# BK8000L_BREADBOARD_BUDDY.net
KiCad netlist of a schematic drawn in EAGLE
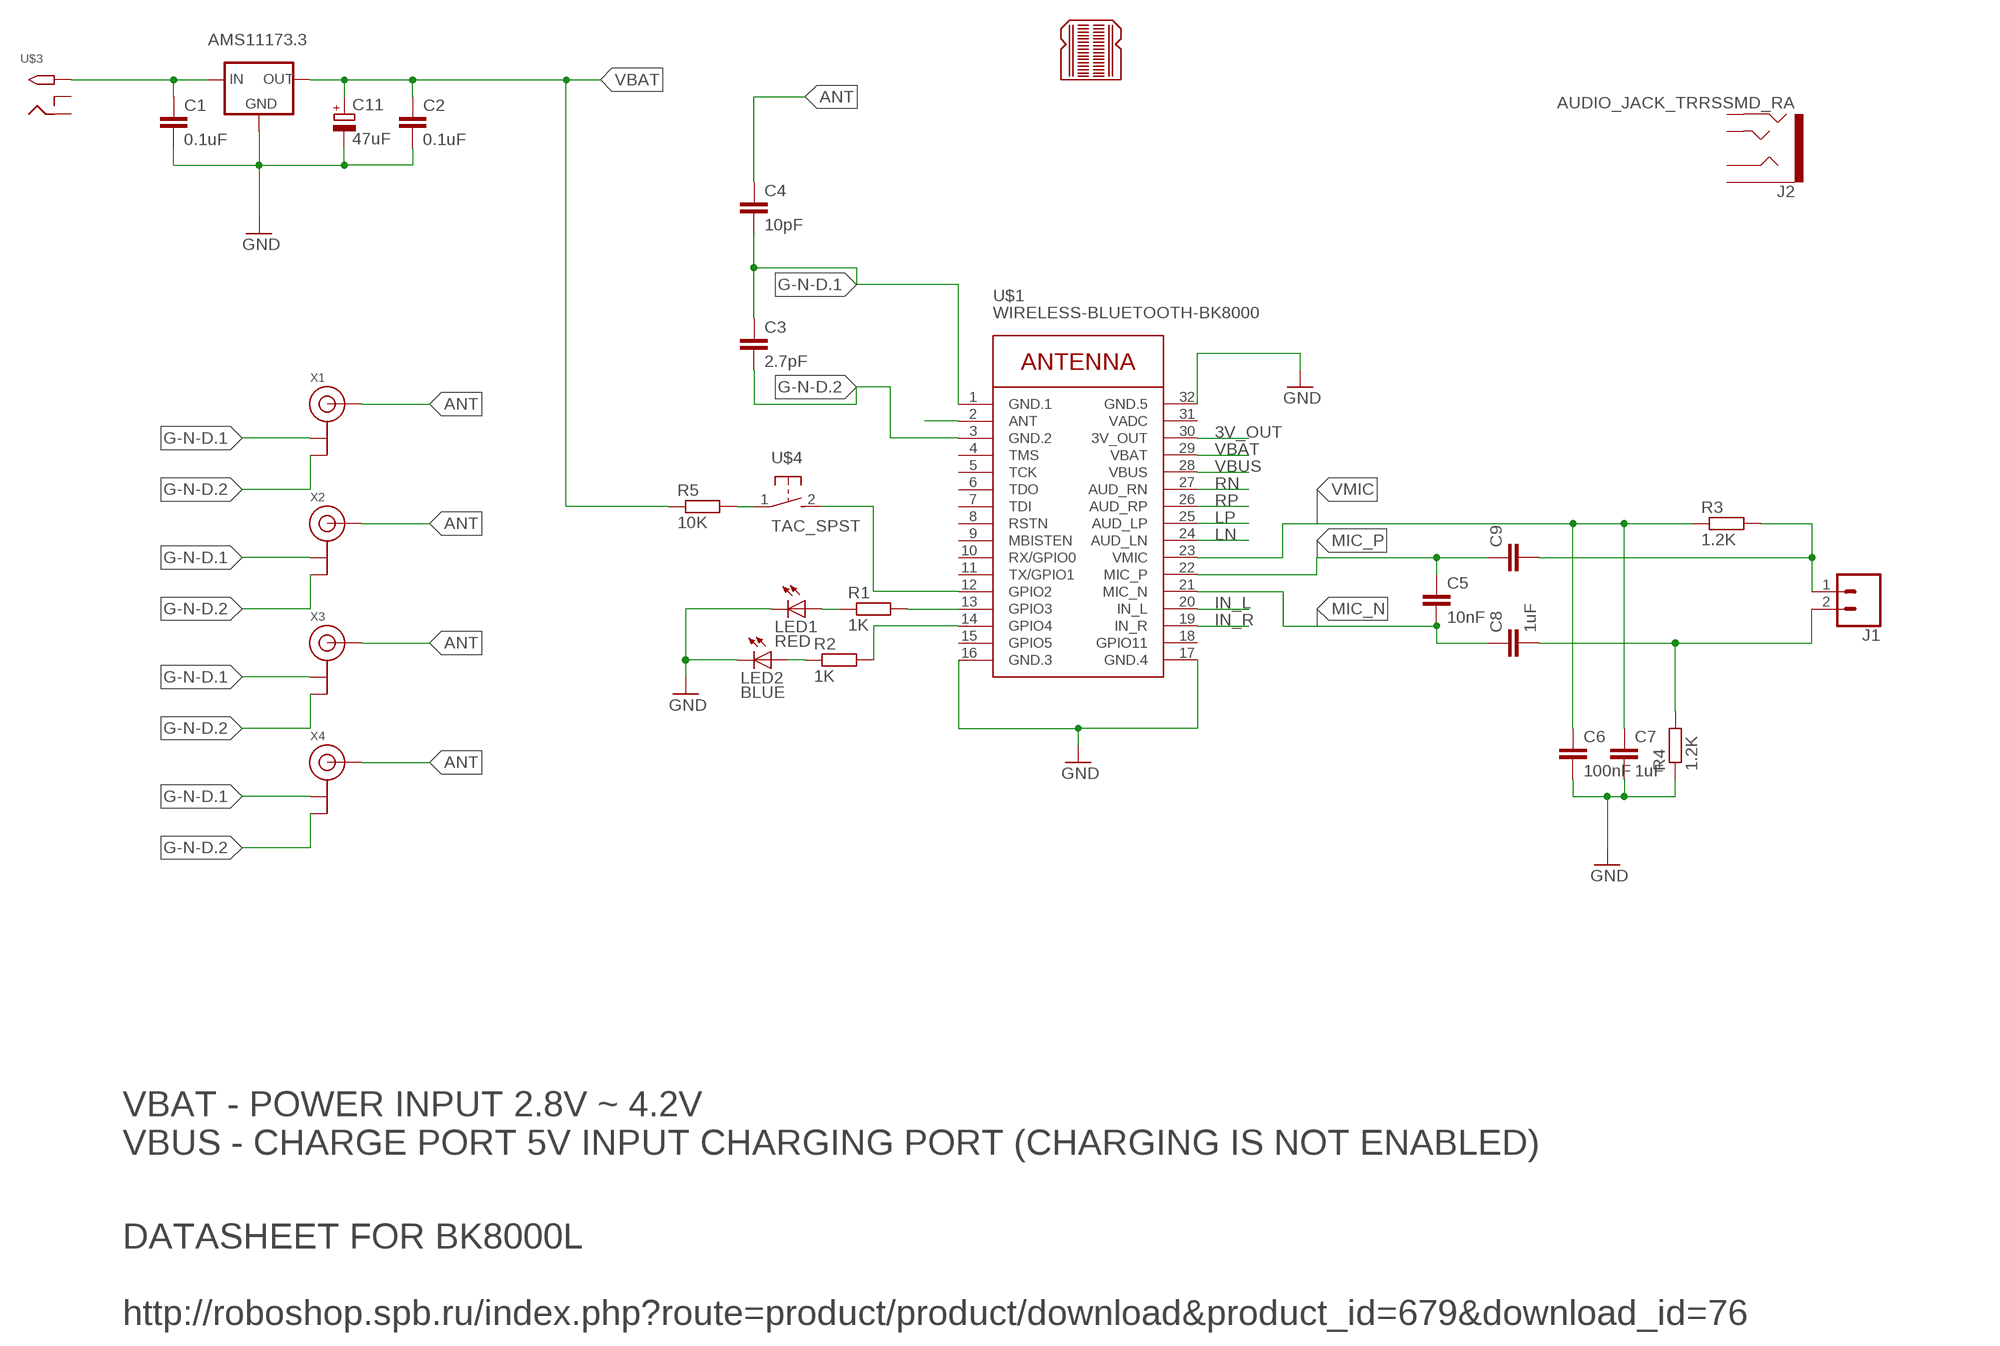
[diagram p0: schematic, sheet 1]

(export (version "E")
  (design (tool "Eeschema 10.0.6"))
  (components
    (comp (ref "C1")
      (value "0.1uF")
      (footprint "eagle-import:C1206")
      (libsource (lib "eagle-import") (part "C-EUC1206"))
    )
    (comp (ref "C2")
      (value "0.1uF")
      (footprint "eagle-import:C1206")
      (libsource (lib "eagle-import") (part "C-EUC1206"))
    )
    (comp (ref "C3")
      (value "2.7pF")
      (footprint "eagle-import:C1206")
      (libsource (lib "eagle-import") (part "C-EUC1206"))
    )
    (comp (ref "C4")
      (value "10pF")
      (footprint "eagle-import:C1206")
      (libsource (lib "eagle-import") (part "C-EUC1206"))
    )
    (comp (ref "C5")
      (value "10nF")
      (footprint "eagle-import:C0603")
      (libsource (lib "eagle-import") (part "C-EUC0603"))
    )
    (comp (ref "C6")
      (value "100nF")
      (footprint "eagle-import:C0603")
      (libsource (lib "eagle-import") (part "C-EUC0603"))
    )
    (comp (ref "C7")
      (value "1uF")
      (footprint "eagle-import:C0603")
      (libsource (lib "eagle-import") (part "C-EUC0603"))
    )
    (comp (ref "C8")
      (value "1uF")
      (footprint "eagle-import:C0603")
      (libsource (lib "eagle-import") (part "C-EUC0603"))
    )
    (comp (ref "C9")
      (value "C-EUC0603")
      (footprint "eagle-import:C0603")
      (libsource (lib "eagle-import") (part "C-EUC0603"))
    )
    (comp (ref "C11")
      (value "47uF")
      (footprint "eagle-import:SMC_D")
      (libsource (lib "eagle-import") (part "CPOL-EUSMCD"))
    )
    (comp (ref "J1")
      (value "CONN_02LOCK")
      (footprint "eagle-import:1X02_LOCK")
      (libsource (lib "eagle-import") (part "CONN_02LOCK"))
    )
    (comp (ref "J2")
      (value "AUDIO_JACK_TRRSSMD_RA")
      (footprint "eagle-import:AUDIO_JACK_3.5MM_TRRS_SMD_RA")
      (libsource (lib "eagle-import") (part "AUDIO_JACK_TRRSSMD_RA"))
    )
    (comp (ref "LED1")
      (value "RED")
      (footprint "eagle-import:CHIPLED_1206")
      (libsource (lib "eagle-import") (part "LEDCHIPLED_1206"))
    )
    (comp (ref "LED2")
      (value "BLUE")
      (footprint "eagle-import:CHIPLED_1206")
      (libsource (lib "eagle-import") (part "LEDCHIPLED_1206"))
    )
    (comp (ref "LOGO1")
      (value "BREADBOARD_PATTERN")
      (footprint "eagle-import:BREADBOARD_SPACING")
      (libsource (lib "eagle-import") (part "BREADBOARD_PATTERN"))
    )
    (comp (ref "R1")
      (value "1K")
      (footprint "eagle-import:R1206")
      (libsource (lib "eagle-import") (part "R-EU_R1206"))
    )
    (comp (ref "R2")
      (value "1K")
      (footprint "eagle-import:R1206")
      (libsource (lib "eagle-import") (part "R-EU_R1206"))
    )
    (comp (ref "R3")
      (value "1.2K")
      (footprint "eagle-import:R0603")
      (libsource (lib "eagle-import") (part "R-EU_R0603"))
    )
    (comp (ref "R4")
      (value "1.2K")
      (footprint "eagle-import:R0603")
      (libsource (lib "eagle-import") (part "R-EU_R0603"))
    )
    (comp (ref "R5")
      (value "10K")
      (footprint "eagle-import:R0603")
      (libsource (lib "eagle-import") (part "R-EU_R0603"))
    )
    (comp (ref "U$1")
      (value "WIRELESS-BLUETOOTH-BK8000")
      (footprint "eagle-import:WIRELESS-BLUETOOTH-BK8000")
      (libsource (lib "eagle-import") (part "WIRELESS-BLUETOOTH-BK8000"))
    )
    (comp (ref "U$2")
      (value "AMS11173.3")
      (footprint "eagle-import:SOT223")
      (libsource (lib "eagle-import") (part "AMS11173.3"))
    )
    (comp (ref "U$3")
      (value "2.1MMJACKMTS")
      (footprint "eagle-import:PJ-102B")
      (libsource (lib "eagle-import") (part "2.1MMJACKMTS"))
    )
    (comp (ref "U$4")
      (value "TAC_SPST")
      (footprint "eagle-import:TACTILE-SPST")
      (libsource (lib "eagle-import") (part "TAC_SPST"))
    )
    (comp (ref "X1")
      (value "ANTENNA_U.FL")
      (footprint "eagle-import:U.FL")
      (libsource (lib "eagle-import") (part "ANTENNA_U.FL"))
    )
    (comp (ref "X2")
      (value "ANTENNA_U.FL")
      (footprint "eagle-import:U.FL")
      (libsource (lib "eagle-import") (part "ANTENNA_U.FL"))
    )
    (comp (ref "X3")
      (value "ANTENNA_U.FL")
      (footprint "eagle-import:U.FL")
      (libsource (lib "eagle-import") (part "ANTENNA_U.FL"))
    )
    (comp (ref "X4")
      (value "ANTENNA_U.FL")
      (footprint "eagle-import:U.FL")
      (libsource (lib "eagle-import") (part "ANTENNA_U.FL"))
    )
  )
  (nets
    (net (code "1") (name "/3V_OUT") (class "Default")
      (node (ref "U$1") (pin "30") (pinfunction "3V_OUT_30") (pintype "power_in"))
    )
    (net (code "2") (name "/IN_L") (class "Default")
      (node (ref "U$1") (pin "20") (pinfunction "IN_L_20") (pintype "input"))
    )
    (net (code "3") (name "/IN_R") (class "Default")
      (node (ref "U$1") (pin "19") (pinfunction "IN_R_19") (pintype "input"))
    )
    (net (code "4") (name "/LN") (class "Default")
      (node (ref "U$1") (pin "24") (pinfunction "AUD_LN_24") (pintype "output"))
    )
    (net (code "5") (name "/LP") (class "Default")
      (node (ref "U$1") (pin "25") (pinfunction "AUD_LP_25") (pintype "output"))
    )
    (net (code "6") (name "/RN") (class "Default")
      (node (ref "U$1") (pin "27") (pinfunction "AUD_RN_27") (pintype "output"))
    )
    (net (code "7") (name "/RP") (class "Default")
      (node (ref "U$1") (pin "26") (pinfunction "AUD_RP_26") (pintype "output"))
    )
    (net (code "8") (name "/VADC") (class "Default")
      (node (ref "U$1") (pin "31") (pinfunction "VADC_31") (pintype "power_in"))
    )
    (net (code "9") (name "/VBUS") (class "Default")
      (node (ref "U$1") (pin "28") (pinfunction "VBUS_28") (pintype "passive"))
    )
    (net (code "10") (name "ANT") (class "Default")
      (node (ref "C4") (pin "1") (pinfunction "1_1") (pintype "passive"))
      (node (ref "U$1") (pin "2") (pinfunction "ANT_2") (pintype "passive"))
      (node (ref "X1") (pin "3") (pinfunction "SIGNAL_3") (pintype "passive"))
      (node (ref "X2") (pin "3") (pinfunction "SIGNAL_3") (pintype "passive"))
      (node (ref "X3") (pin "3") (pinfunction "SIGNAL_3") (pintype "passive"))
      (node (ref "X4") (pin "3") (pinfunction "SIGNAL_3") (pintype "passive"))
    )
    (net (code "11") (name "G-N-D.1") (class "Default")
      (node (ref "C3") (pin "1") (pinfunction "1_1") (pintype "passive"))
      (node (ref "C4") (pin "2") (pinfunction "2_2") (pintype "passive"))
      (node (ref "U$1") (pin "1") (pinfunction "GND.1_1") (pintype "power_in"))
      (node (ref "X1") (pin "1") (pinfunction "GND_1") (pintype "passive"))
      (node (ref "X2") (pin "1") (pinfunction "GND_1") (pintype "passive"))
      (node (ref "X3") (pin "1") (pinfunction "GND_1") (pintype "passive"))
      (node (ref "X4") (pin "1") (pinfunction "GND_1") (pintype "passive"))
    )
    (net (code "12") (name "G-N-D.2") (class "Default")
      (node (ref "C3") (pin "2") (pinfunction "2_2") (pintype "passive"))
      (node (ref "U$1") (pin "3") (pinfunction "GND.2_3") (pintype "power_in"))
      (node (ref "X1") (pin "2") (pinfunction "GND_2") (pintype "passive"))
      (node (ref "X2") (pin "2") (pinfunction "GND_2") (pintype "passive"))
      (node (ref "X3") (pin "2") (pinfunction "GND_2") (pintype "passive"))
      (node (ref "X4") (pin "2") (pinfunction "GND_2") (pintype "passive"))
    )
    (net (code "13") (name "GND") (class "Default")
      (node (ref "C1") (pin "2") (pinfunction "2_2") (pintype "passive"))
      (node (ref "C11") (pin "-") (pinfunction "-_-") (pintype "passive"))
      (node (ref "C2") (pin "2") (pinfunction "2_2") (pintype "passive"))
      (node (ref "C6") (pin "2") (pinfunction "2_2") (pintype "passive"))
      (node (ref "C7") (pin "2") (pinfunction "2_2") (pintype "passive"))
      (node (ref "LED1") (pin "C") (pinfunction "C_C") (pintype "passive"))
      (node (ref "LED2") (pin "C") (pinfunction "C_C") (pintype "passive"))
      (node (ref "R4") (pin "1") (pinfunction "1_1") (pintype "passive"))
      (node (ref "U$1") (pin "16") (pinfunction "GND.3_16") (pintype "power_in"))
      (node (ref "U$1") (pin "17") (pinfunction "GND.4_17") (pintype "power_in"))
      (node (ref "U$1") (pin "32") (pinfunction "GND.5_32") (pintype "power_in"))
      (node (ref "U$2") (pin "1") (pinfunction "GND_1") (pintype "input"))
    )
    (net (code "14") (name "MIC_N") (class "Default")
      (node (ref "C5") (pin "2") (pinfunction "2_2") (pintype "passive"))
      (node (ref "C8") (pin "1") (pinfunction "1_1") (pintype "passive"))
      (node (ref "U$1") (pin "21") (pinfunction "MIC_N_21") (pintype "input"))
    )
    (net (code "15") (name "MIC_P") (class "Default")
      (node (ref "C5") (pin "1") (pinfunction "1_1") (pintype "passive"))
      (node (ref "C9") (pin "1") (pinfunction "1_1") (pintype "passive"))
      (node (ref "U$1") (pin "22") (pinfunction "MIC_P_22") (pintype "input"))
    )
    (net (code "16") (name "Net-(C8-Pad2)") (class "Default")
      (node (ref "C8") (pin "2") (pinfunction "2_2") (pintype "passive"))
      (node (ref "J1") (pin "2") (pinfunction "2_2") (pintype "passive"))
      (node (ref "R4") (pin "2") (pinfunction "2_2") (pintype "passive"))
    )
    (net (code "17") (name "Net-(C9-Pad2)") (class "Default")
      (node (ref "C9") (pin "2") (pinfunction "2_2") (pintype "passive"))
      (node (ref "J1") (pin "1") (pinfunction "1_1") (pintype "passive"))
      (node (ref "R3") (pin "2") (pinfunction "2_2") (pintype "passive"))
    )
    (net (code "18") (name "Net-(LED1-PadA)") (class "Default")
      (node (ref "LED1") (pin "A") (pinfunction "A_A") (pintype "passive"))
      (node (ref "R1") (pin "1") (pinfunction "1_1") (pintype "passive"))
    )
    (net (code "19") (name "Net-(LED2-PadA)") (class "Default")
      (node (ref "LED2") (pin "A") (pinfunction "A_A") (pintype "passive"))
      (node (ref "R2") (pin "1") (pinfunction "1_1") (pintype "passive"))
    )
    (net (code "20") (name "Net-(R5-Pad2)") (class "Default")
      (node (ref "R5") (pin "2") (pinfunction "2_2") (pintype "passive"))
      (node (ref "U$4") (pin "1") (pinfunction "1_1") (pintype "passive"))
    )
    (net (code "21") (name "Net-(U$1-GPIO2)") (class "Default")
      (node (ref "U$1") (pin "12") (pinfunction "GPIO2_12") (pintype "bidirectional"))
      (node (ref "U$4") (pin "2") (pinfunction "2_2") (pintype "passive"))
    )
    (net (code "22") (name "Net-(U$1-GPIO3)") (class "Default")
      (node (ref "R1") (pin "2") (pinfunction "2_2") (pintype "passive"))
      (node (ref "U$1") (pin "13") (pinfunction "GPIO3_13") (pintype "bidirectional"))
    )
    (net (code "23") (name "Net-(U$1-GPIO4)") (class "Default")
      (node (ref "R2") (pin "2") (pinfunction "2_2") (pintype "passive"))
      (node (ref "U$1") (pin "14") (pinfunction "GPIO4_14") (pintype "bidirectional"))
    )
    (net (code "24") (name "Net-(U$2-IN)") (class "Default")
      (node (ref "C1") (pin "1") (pinfunction "1_1") (pintype "passive"))
      (node (ref "U$2") (pin "3") (pinfunction "IN_3") (pintype "input"))
      (node (ref "U$3") (pin "TIP") (pinfunction "TIP_TIP") (pintype "bidirectional"))
    )
    (net (code "25") (name "VBAT") (class "Default")
      (node (ref "C11") (pin "+") (pinfunction "+_+") (pintype "passive"))
      (node (ref "C2") (pin "1") (pinfunction "1_1") (pintype "passive"))
      (node (ref "R5") (pin "1") (pinfunction "1_1") (pintype "passive"))
      (node (ref "U$1") (pin "29") (pinfunction "VBAT_29") (pintype "passive"))
      (node (ref "U$2") (pin "2") (pinfunction "OUT_2") (pintype "passive"))
      (node (ref "U$2") (pin "4") (pinfunction "OUT_4") (pintype "passive"))
    )
    (net (code "26") (name "VMIC") (class "Default")
      (node (ref "C6") (pin "1") (pinfunction "1_1") (pintype "passive"))
      (node (ref "C7") (pin "1") (pinfunction "1_1") (pintype "passive"))
      (node (ref "R3") (pin "1") (pinfunction "1_1") (pintype "passive"))
      (node (ref "U$1") (pin "23") (pinfunction "VMIC_23") (pintype "passive"))
    )
    (net (code "27") (name "unconnected-(J2-PadEARTH)") (class "Default")
      (node (ref "J2") (pin "EARTH") (pinfunction "EARTH_EARTH") (pintype "bidirectional"))
    )
    (net (code "28") (name "unconnected-(J2-PadRING1)") (class "Default")
      (node (ref "J2") (pin "RING1") (pinfunction "RING1_RING1") (pintype "bidirectional"))
    )
    (net (code "29") (name "unconnected-(J2-PadRING2)") (class "Default")
      (node (ref "J2") (pin "RING2") (pinfunction "RING2_RING2") (pintype "bidirectional"))
    )
    (net (code "30") (name "unconnected-(J2-PadTIP)") (class "Default")
      (node (ref "J2") (pin "TIP") (pinfunction "TIP_TIP") (pintype "bidirectional"))
    )
    (net (code "31") (name "unconnected-(U$1-GPIO5-Pad15)") (class "Default")
      (node (ref "U$1") (pin "15") (pinfunction "GPIO5_15") (pintype "bidirectional"))
    )
    (net (code "32") (name "unconnected-(U$1-GPIO11-Pad18)") (class "Default")
      (node (ref "U$1") (pin "18") (pinfunction "GPIO11_18") (pintype "bidirectional"))
    )
    (net (code "33") (name "unconnected-(U$1-MBISTEN-Pad9)") (class "Default")
      (node (ref "U$1") (pin "9") (pinfunction "MBISTEN_9") (pintype "bidirectional"))
    )
    (net (code "34") (name "unconnected-(U$1-RSTN-Pad8)") (class "Default")
      (node (ref "U$1") (pin "8") (pinfunction "RSTN_8") (pintype "bidirectional"))
    )
    (net (code "35") (name "unconnected-(U$1-RX{slash}GPIO0-Pad10)") (class "Default")
      (node (ref "U$1") (pin "10") (pinfunction "RX/GPIO0_10") (pintype "bidirectional"))
    )
    (net (code "36") (name "unconnected-(U$1-TCK-Pad5)") (class "Default")
      (node (ref "U$1") (pin "5") (pinfunction "TCK_5") (pintype "bidirectional"))
    )
    (net (code "37") (name "unconnected-(U$1-TDI-Pad7)") (class "Default")
      (node (ref "U$1") (pin "7") (pinfunction "TDI_7") (pintype "bidirectional"))
    )
    (net (code "38") (name "unconnected-(U$1-TDO-Pad6)") (class "Default")
      (node (ref "U$1") (pin "6") (pinfunction "TDO_6") (pintype "bidirectional"))
    )
    (net (code "39") (name "unconnected-(U$1-TMS-Pad4)") (class "Default")
      (node (ref "U$1") (pin "4") (pinfunction "TMS_4") (pintype "bidirectional"))
    )
    (net (code "40") (name "unconnected-(U$1-TX{slash}GPIO1-Pad11)") (class "Default")
      (node (ref "U$1") (pin "11") (pinfunction "TX/GPIO1_11") (pintype "bidirectional"))
    )
    (net (code "41") (name "unconnected-(U$3-PadRING)") (class "Default")
      (node (ref "U$3") (pin "RING") (pinfunction "RING_RING") (pintype "bidirectional"))
    )
    (net (code "42") (name "unconnected-(U$3-PadRING_SW)") (class "Default")
      (node (ref "U$3") (pin "RING_SW") (pinfunction "RING_SW_RING_SW") (pintype "bidirectional"))
    )
  )
)
